# CPN_v2.net
KiCad netlist of a schematic drawn in EAGLE
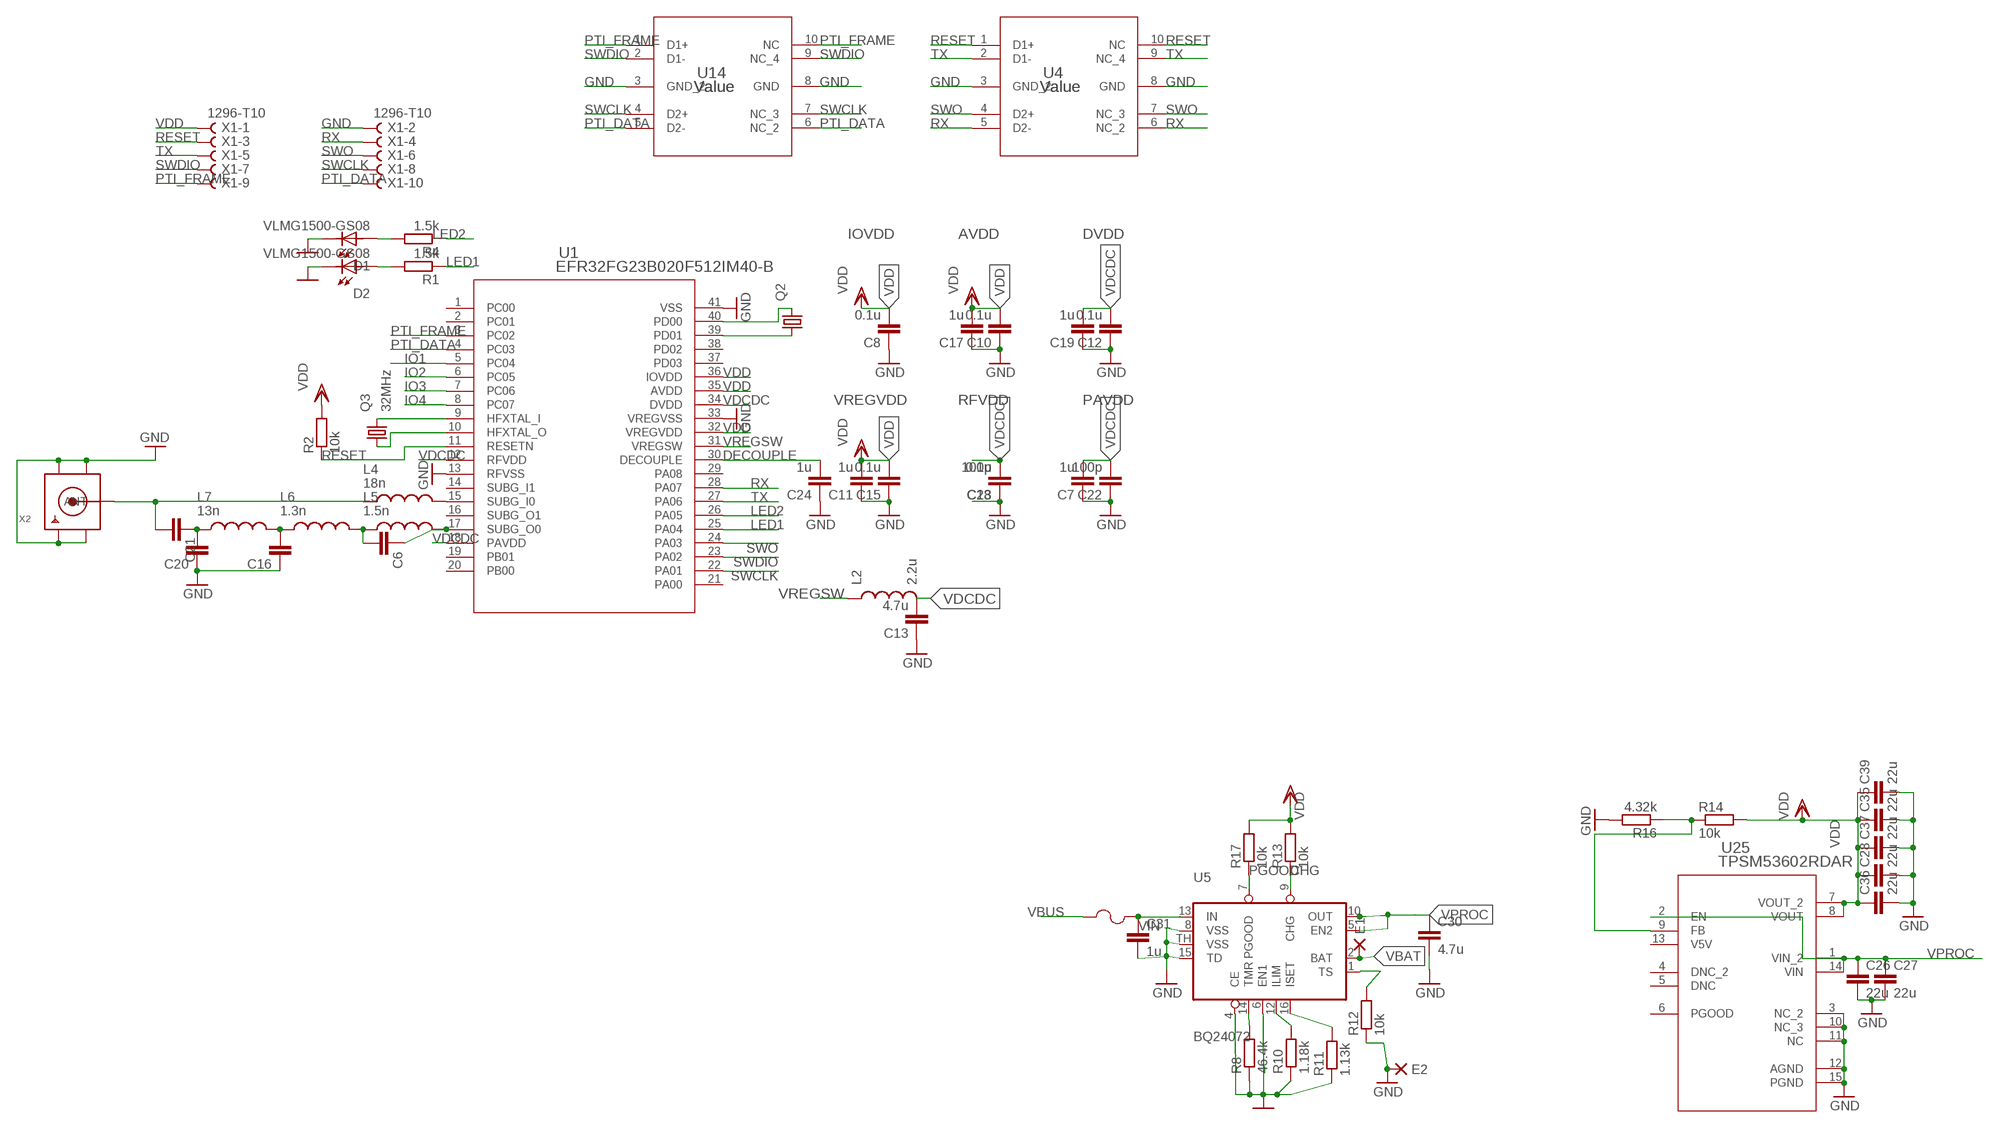
[diagram p0: schematic, sheet 1, part 1 of 2]
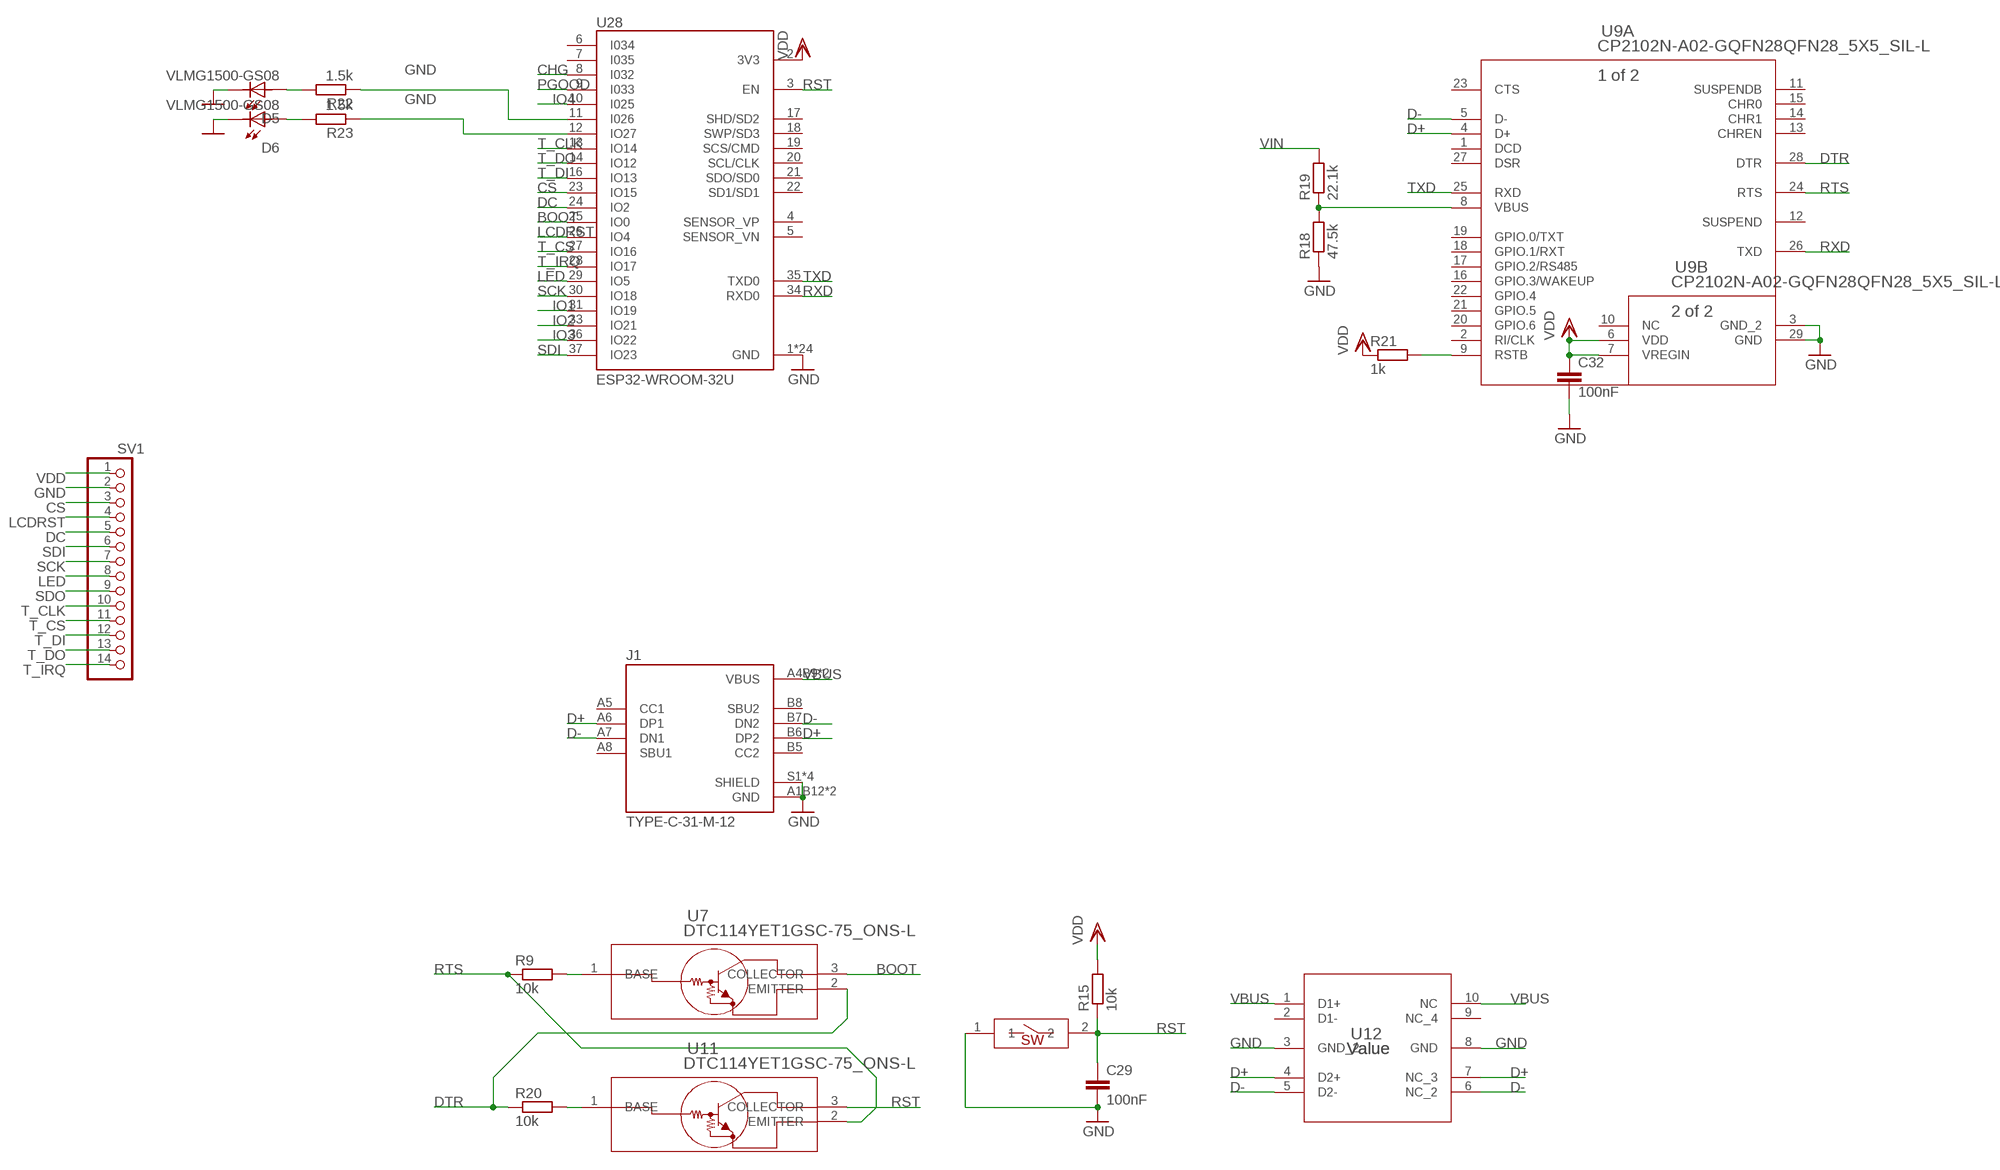
[diagram p1: schematic, sheet 1, part 2 of 2]

(export (version "E")
  (design (tool "Eeschema 10.0.6"))
  (components
    (comp (ref "C6")
      (value "1.9p")
      (footprint "eagle-import:C0402")
      (libsource (lib "eagle-import") (part "CC0402"))
    )
    (comp (ref "C7")
      (value "1u")
      (footprint "eagle-import:C0402")
      (libsource (lib "eagle-import") (part "CC0402"))
    )
    (comp (ref "C8")
      (value "0.1u")
      (footprint "eagle-import:C0402")
      (libsource (lib "eagle-import") (part "CC0402"))
    )
    (comp (ref "C10")
      (value "0.1u")
      (footprint "eagle-import:C0402")
      (libsource (lib "eagle-import") (part "CC0402"))
    )
    (comp (ref "C11")
      (value "1u")
      (footprint "eagle-import:C0402")
      (libsource (lib "eagle-import") (part "CC0402"))
    )
    (comp (ref "C12")
      (value "0.1u")
      (footprint "eagle-import:C0402")
      (libsource (lib "eagle-import") (part "CC0402"))
    )
    (comp (ref "C13")
      (value "4.7u")
      (footprint "eagle-import:C0603R")
      (libsource (lib "eagle-import") (part "CC0603R"))
    )
    (comp (ref "C15")
      (value "0.1u")
      (footprint "eagle-import:C0402")
      (libsource (lib "eagle-import") (part "CC0402"))
    )
    (comp (ref "C16")
      (value "7.2p")
      (footprint "eagle-import:C0402")
      (libsource (lib "eagle-import") (part "CC0402"))
    )
    (comp (ref "C17")
      (value "1u")
      (footprint "eagle-import:C0402")
      (libsource (lib "eagle-import") (part "CC0402"))
    )
    (comp (ref "C18")
      (value "0.1u")
      (footprint "eagle-import:C0402")
      (libsource (lib "eagle-import") (part "CC0402"))
    )
    (comp (ref "C19")
      (value "1u")
      (footprint "eagle-import:C0402")
      (libsource (lib "eagle-import") (part "CC0402"))
    )
    (comp (ref "C20")
      (value "1.3p")
      (footprint "eagle-import:C0402")
      (libsource (lib "eagle-import") (part "CC0402"))
    )
    (comp (ref "C21")
      (value "220p")
      (footprint "eagle-import:C0402")
      (libsource (lib "eagle-import") (part "CC0402"))
    )
    (comp (ref "C22")
      (value "100p")
      (footprint "eagle-import:C0402")
      (libsource (lib "eagle-import") (part "CC0402"))
    )
    (comp (ref "C23")
      (value "100p")
      (footprint "eagle-import:C0402")
      (libsource (lib "eagle-import") (part "CC0402"))
    )
    (comp (ref "C24")
      (value "1u")
      (footprint "eagle-import:C0402")
      (libsource (lib "eagle-import") (part "CC0402"))
    )
    (comp (ref "C26")
      (value "22u")
      (footprint "eagle-import:C0603R")
      (libsource (lib "eagle-import") (part "CC0603R"))
    )
    (comp (ref "C27")
      (value "22u")
      (footprint "eagle-import:C0603R")
      (libsource (lib "eagle-import") (part "CC0603R"))
    )
    (comp (ref "C28")
      (value "22u")
      (footprint "eagle-import:C0603R")
      (libsource (lib "eagle-import") (part "CC0603R"))
    )
    (comp (ref "C29")
      (value "100nF")
      (footprint "eagle-import:C0402")
      (libsource (lib "eagle-import") (part "CC0402"))
    )
    (comp (ref "C30")
      (value "4.7u")
      (footprint "eagle-import:C0402")
      (libsource (lib "eagle-import") (part "CC0402"))
    )
    (comp (ref "C31")
      (value "1u")
      (footprint "eagle-import:C0402")
      (libsource (lib "eagle-import") (part "CC0402"))
    )
    (comp (ref "C32")
      (value "100nF")
      (footprint "eagle-import:C0402")
      (libsource (lib "eagle-import") (part "CC0402"))
    )
    (comp (ref "C35")
      (value "22u")
      (footprint "eagle-import:C0603R")
      (libsource (lib "eagle-import") (part "CC0603R"))
    )
    (comp (ref "C36")
      (value "22u")
      (footprint "eagle-import:C0603R")
      (libsource (lib "eagle-import") (part "CC0603R"))
    )
    (comp (ref "C37")
      (value "22u")
      (footprint "eagle-import:C0603R")
      (libsource (lib "eagle-import") (part "CC0603R"))
    )
    (comp (ref "C39")
      (value "22u")
      (footprint "eagle-import:C0603R")
      (libsource (lib "eagle-import") (part "CC0603R"))
    )
    (comp (ref "D1")
      (value "VLMG1500-GS08")
      (footprint "eagle-import:LEDC1005X35N")
      (fields (field (name "MF") "Vishay"))
      (libsource (lib "eagle-import") (part "VLMG1500-GS08"))
    )
    (comp (ref "D2")
      (value "VLMG1500-GS08")
      (footprint "eagle-import:LEDC1005X35N")
      (fields (field (name "MF") "Vishay"))
      (libsource (lib "eagle-import") (part "VLMG1500-GS08"))
    )
    (comp (ref "D5")
      (value "VLMG1500-GS08")
      (footprint "eagle-import:LEDC1005X35N")
      (fields (field (name "MF") "Vishay"))
      (libsource (lib "eagle-import") (part "VLMG1500-GS08"))
    )
    (comp (ref "D6")
      (value "VLMG1500-GS08")
      (footprint "eagle-import:LEDC1005X35N")
      (fields (field (name "MF") "Vishay"))
      (libsource (lib "eagle-import") (part "VLMG1500-GS08"))
    )
    (comp (ref "E1")
      (value "DPADS_PAD-0400-S")
      (footprint "eagle-import:DPADS_0400-S")
      (libsource (lib "eagle-import") (part "DPADS_PAD-0400-S"))
    )
    (comp (ref "E2")
      (value "DPADS_PAD-0400-S")
      (footprint "eagle-import:DPADS_0400-S")
      (libsource (lib "eagle-import") (part "DPADS_PAD-0400-S"))
    )
    (comp (ref "F2")
      (value "1210L050YR1210LSERIES_LTF-L")
      (footprint "eagle-import:1210LSERIES_LTF-L")
      (fields (field (name "MANUFACTURER_PART_NUMBER") "1210L050YR"))
      (libsource (lib "eagle-import") (part "1210L050YR1210LSERIES_LTF-L"))
    )
    (comp (ref "J1")
      (value "TYPE-C-31-M-12")
      (footprint "eagle-import:HRO_TYPE-C-31-M-12")
      (fields (field (name "MF") "HRO Electronics Co., Ltd."))
      (libsource (lib "eagle-import") (part "TYPE-C-31-M-12"))
    )
    (comp (ref "L2")
      (value "2.2u")
      (footprint "eagle-import:L0603")
      (libsource (lib "eagle-import") (part "INDUCTOR"))
    )
    (comp (ref "L4")
      (value "18n")
      (footprint "eagle-import:INDC0402X26N")
      (fields (field (name "MF") "TDK") (field (name "MP") "MHQ0402P7N5JT000"))
      (libsource (lib "eagle-import") (part "MHQ0402P7N5JT000"))
    )
    (comp (ref "L5")
      (value "1.5n")
      (footprint "eagle-import:INDC0402X26N")
      (fields (field (name "MF") "TDK") (field (name "MP") "MHQ0402P7N5JT000"))
      (libsource (lib "eagle-import") (part "MHQ0402P7N5JT000"))
    )
    (comp (ref "L6")
      (value "1.3n")
      (footprint "eagle-import:INDC0402X26N")
      (fields (field (name "MF") "TDK") (field (name "MP") "MHQ0402P7N5JT000"))
      (libsource (lib "eagle-import") (part "MHQ0402P7N5JT000"))
    )
    (comp (ref "L7")
      (value "13n")
      (footprint "eagle-import:INDC0402X26N")
      (fields (field (name "MF") "TDK") (field (name "MP") "MHQ0402P7N5JT000"))
      (libsource (lib "eagle-import") (part "MHQ0402P7N5JT000"))
    )
    (comp (ref "Q2")
      (value "KX-327-RT")
      (footprint "eagle-import:2.0X1.2")
      (libsource (lib "eagle-import") (part "KX-327-RT"))
    )
    (comp (ref "Q3")
      (value "32MHz")
      (footprint "eagle-import:2.0X1.6_KX-5")
      (libsource (lib "eagle-import") (part "KX-5"))
    )
    (comp (ref "R1")
      (value "1.5k")
      (footprint "eagle-import:R0402")
      (libsource (lib "eagle-import") (part "RR0402"))
    )
    (comp (ref "R2")
      (value "10k")
      (footprint "eagle-import:R0402")
      (libsource (lib "eagle-import") (part "RR0402"))
    )
    (comp (ref "R4")
      (value "1.5k")
      (footprint "eagle-import:R0402")
      (libsource (lib "eagle-import") (part "RR0402"))
    )
    (comp (ref "R8")
      (value "46.4k")
      (footprint "eagle-import:R0402")
      (libsource (lib "eagle-import") (part "RR0402"))
    )
    (comp (ref "R9")
      (value "10k")
      (footprint "eagle-import:R0402")
      (libsource (lib "eagle-import") (part "RR0402"))
    )
    (comp (ref "R10")
      (value "1.18k")
      (footprint "eagle-import:R0402")
      (libsource (lib "eagle-import") (part "RR0402"))
    )
    (comp (ref "R11")
      (value "1.13k")
      (footprint "eagle-import:R0402")
      (libsource (lib "eagle-import") (part "RR0402"))
    )
    (comp (ref "R12")
      (value "10k")
      (footprint "eagle-import:R0402")
      (libsource (lib "eagle-import") (part "RR0402"))
    )
    (comp (ref "R13")
      (value "10k")
      (footprint "eagle-import:R0402")
      (libsource (lib "eagle-import") (part "RR0402"))
    )
    (comp (ref "R14")
      (value "10k")
      (footprint "eagle-import:R0402")
      (libsource (lib "eagle-import") (part "RR0402"))
    )
    (comp (ref "R15")
      (value "10k")
      (footprint "eagle-import:R0402")
      (libsource (lib "eagle-import") (part "RR0402"))
    )
    (comp (ref "R16")
      (value "4.32k")
      (footprint "eagle-import:R0402")
      (libsource (lib "eagle-import") (part "RR0402"))
    )
    (comp (ref "R17")
      (value "10k")
      (footprint "eagle-import:R0402")
      (libsource (lib "eagle-import") (part "RR0402"))
    )
    (comp (ref "R18")
      (value "47.5k")
      (footprint "eagle-import:R0402")
      (libsource (lib "eagle-import") (part "RR0402"))
    )
    (comp (ref "R19")
      (value "22.1k")
      (footprint "eagle-import:R0402")
      (libsource (lib "eagle-import") (part "RR0402"))
    )
    (comp (ref "R20")
      (value "10k")
      (footprint "eagle-import:R0402")
      (libsource (lib "eagle-import") (part "RR0402"))
    )
    (comp (ref "R21")
      (value "1k")
      (footprint "eagle-import:R0402")
      (libsource (lib "eagle-import") (part "RR0402"))
    )
    (comp (ref "R22")
      (value "1.5k")
      (footprint "eagle-import:R0402")
      (libsource (lib "eagle-import") (part "RR0402"))
    )
    (comp (ref "R23")
      (value "1.5k")
      (footprint "eagle-import:R0402")
      (libsource (lib "eagle-import") (part "RR0402"))
    )
    (comp (ref "RESET")
      (value "SMDSWITCH")
      (footprint "eagle-import:RESC4217X170")
      (libsource (lib "eagle-import") (part "SMDSWITCH"))
    )
    (comp (ref "SV1")
      (value "PINHD-1X14")
      (footprint "eagle-import:1X14")
      (libsource (lib "eagle-import") (part "PINHD-1X14"))
    )
    (comp (ref "U1")
      (value "EFR32FG23B020F512IM40-B")
      (footprint "eagle-import:QFN_40_SIL")
      (fields (field (name "COPYRIGHT") "Copyright (C) 2022 Ultra Librarian. All rights reserved."))
      (libsource (lib "eagle-import") (part "EFR32FG23B020F512IM40-B"))
    )
    (comp (ref "U4")
      (value "Value")
      (footprint "eagle-import:DQA0010A")
      (fields (field (name "MANUFACTURER") "Texas Instruments") (field (name "PARTNUMBER") "ESD204DQAR"))
      (libsource (lib "eagle-import") (part "ESD204DQAR"))
    )
    (comp (ref "U5")
      (value "BQ24072")
      (footprint "eagle-import:S-PVQFN-N16")
      (libsource (lib "eagle-import") (part "BQ24072"))
    )
    (comp (ref "U7")
      (value "DTC114YET1GSC-75_ONS-L")
      (footprint "eagle-import:SC-75_ONS-L")
      (fields
        (field (name "MANUFACTURER_PART_NUMBER") "DTC114YET1G")
        (field (name "COPYRIGHT") "Copyright (C) 2018 Accelerated Designs. All rights reserved")
      )
      (libsource (lib "eagle-import") (part "DTC114YET1GSC-75_ONS-L"))
    )
    (comp (ref "U9")
      (value "CP2102N-A02-GQFN28QFN28_5X5_SIL-L")
      (footprint "eagle-import:QFN28_5X5_SIL-L")
      (fields
        (field (name "MANUFACTURER_PART_NUMBER") "CP2102N-A02-GQFN28")
        (field (name "COPYRIGHT") "Copyright (C) 2018 Accelerated Designs. All rights reserved")
      )
      (libsource (lib "eagle-import") (part "CP2102N-A02-GQFN28QFN28_5X5_SIL-L"))
    )
    (comp (ref "U11")
      (value "DTC114YET1GSC-75_ONS-L")
      (footprint "eagle-import:SC-75_ONS-L")
      (fields
        (field (name "MANUFACTURER_PART_NUMBER") "DTC114YET1G")
        (field (name "COPYRIGHT") "Copyright (C) 2018 Accelerated Designs. All rights reserved")
      )
      (libsource (lib "eagle-import") (part "DTC114YET1GSC-75_ONS-L"))
    )
    (comp (ref "U12")
      (value "Value")
      (footprint "eagle-import:DQA0010A")
      (fields (field (name "MANUFACTURER") "Texas Instruments") (field (name "PARTNUMBER") "ESD204DQAR"))
      (libsource (lib "eagle-import") (part "ESD204DQAR"))
    )
    (comp (ref "U14")
      (value "Value")
      (footprint "eagle-import:DQA0010A")
      (fields (field (name "MANUFACTURER") "Texas Instruments") (field (name "PARTNUMBER") "ESD204DQAR"))
      (libsource (lib "eagle-import") (part "ESD204DQAR"))
    )
    (comp (ref "U25")
      (value "TPSM53602RDAR")
      (footprint "eagle-import:B3QFN15_RDA_TEX")
      (fields (field (name "COPYRIGHT") "Copyright (C) 2018 Accelerated Designs. All rights reserved"))
      (libsource (lib "eagle-import") (part "TPSM53602RDAR"))
    )
    (comp (ref "U28")
      (value "ESP32-WROOM-32U")
      (footprint "eagle-import:XCVR_ESP32-WROOM-32U")
      (fields (field (name "MF") "Espressif Systems"))
      (libsource (lib "eagle-import") (part "ESP32-WROOM-32U"))
    )
    (comp (ref "X1")
      (value "1296-T10")
      (footprint "eagle-import:1296-10")
      (libsource (lib "eagle-import") (part "1296-T10"))
    )
    (comp (ref "X2")
      (value "SMACONNECTOR")
      (footprint "eagle-import:SMA90_DIP")
      (libsource (lib "eagle-import") (part "SMACONNECTOR"))
    )
  )
  (nets
    (net (code "1") (name "/BOOT") (class "Default")
      (node (ref "U28") (pin "25") (pinfunction "IO0_25") (pintype "bidirectional"))
      (node (ref "U7") (pin "3") (pinfunction "COLLECTOR_3") (pintype "output"))
    )
    (net (code "2") (name "/CHG") (class "Default")
      (node (ref "R13") (pin "1") (pinfunction "1_1") (pintype "passive"))
      (node (ref "U28") (pin "8") (pinfunction "I032_8") (pintype "bidirectional"))
      (node (ref "U5") (pin "9") (pinfunction "CHG_9") (pintype "bidirectional"))
    )
    (net (code "3") (name "/CS") (class "Default")
      (node (ref "SV1") (pin "3") (pinfunction "3_3") (pintype "passive"))
      (node (ref "U28") (pin "23") (pinfunction "IO15_23") (pintype "bidirectional"))
    )
    (net (code "4") (name "/D+") (class "Default")
      (node (ref "J1") (pin "A6") (pinfunction "DP1_A6") (pintype "bidirectional"))
      (node (ref "J1") (pin "B6") (pinfunction "DP2_B6") (pintype "bidirectional"))
      (node (ref "U12") (pin "4") (pinfunction "D2+_4") (pintype "bidirectional"))
      (node (ref "U12") (pin "7") (pinfunction "NC_3_7") (pintype "passive"))
      (node (ref "U9") (pin "4") (pinfunction "D+_4") (pintype "input"))
    )
    (net (code "5") (name "/D-") (class "Default")
      (node (ref "J1") (pin "A7") (pinfunction "DN1_A7") (pintype "bidirectional"))
      (node (ref "J1") (pin "B7") (pinfunction "DN2_B7") (pintype "bidirectional"))
      (node (ref "U12") (pin "5") (pinfunction "D2-_5") (pintype "bidirectional"))
      (node (ref "U12") (pin "6") (pinfunction "NC_2_6") (pintype "passive"))
      (node (ref "U9") (pin "5") (pinfunction "D-_5") (pintype "input"))
    )
    (net (code "6") (name "/DC") (class "Default")
      (node (ref "SV1") (pin "5") (pinfunction "5_5") (pintype "passive"))
      (node (ref "U28") (pin "24") (pinfunction "IO2_24") (pintype "bidirectional"))
    )
    (net (code "7") (name "/DECOUPLE") (class "Default")
      (node (ref "C24") (pin "2") (pinfunction "2_2") (pintype "passive"))
      (node (ref "U1") (pin "30") (pinfunction "DECOUPLE_30") (pintype "passive"))
    )
    (net (code "8") (name "/DTR") (class "Default")
      (node (ref "R20") (pin "1") (pinfunction "1_1") (pintype "passive"))
      (node (ref "U7") (pin "2") (pinfunction "EMITTER_2") (pintype "passive"))
      (node (ref "U9") (pin "28") (pinfunction "DTR_28") (pintype "output"))
    )
    (net (code "9") (name "/IO1") (class "Default")
      (node (ref "U1") (pin "5") (pinfunction "PC04_5") (pintype "bidirectional"))
      (node (ref "U28") (pin "31") (pinfunction "IO19_31") (pintype "bidirectional"))
    )
    (net (code "10") (name "/IO2") (class "Default")
      (node (ref "U1") (pin "6") (pinfunction "PC05_6") (pintype "bidirectional"))
      (node (ref "U28") (pin "33") (pinfunction "IO21_33") (pintype "bidirectional"))
    )
    (net (code "11") (name "/IO3") (class "Default")
      (node (ref "U1") (pin "7") (pinfunction "PC06_7") (pintype "bidirectional"))
      (node (ref "U28") (pin "36") (pinfunction "IO22_36") (pintype "bidirectional"))
    )
    (net (code "12") (name "/IO4") (class "Default")
      (node (ref "U1") (pin "8") (pinfunction "PC07_8") (pintype "bidirectional"))
      (node (ref "U28") (pin "10") (pinfunction "I025_10") (pintype "bidirectional"))
    )
    (net (code "13") (name "/LCDRST") (class "Default")
      (node (ref "SV1") (pin "4") (pinfunction "4_4") (pintype "passive"))
      (node (ref "U28") (pin "26") (pinfunction "IO4_26") (pintype "bidirectional"))
    )
    (net (code "14") (name "/LED") (class "Default")
      (node (ref "SV1") (pin "8") (pinfunction "8_8") (pintype "passive"))
      (node (ref "U28") (pin "29") (pinfunction "IO5_29") (pintype "bidirectional"))
    )
    (net (code "15") (name "/LED1") (class "Default")
      (node (ref "R1") (pin "1") (pinfunction "1_1") (pintype "passive"))
      (node (ref "U1") (pin "25") (pinfunction "PA04_25") (pintype "bidirectional"))
    )
    (net (code "16") (name "/LED2") (class "Default")
      (node (ref "R4") (pin "1") (pinfunction "1_1") (pintype "passive"))
      (node (ref "U1") (pin "26") (pinfunction "PA05_26") (pintype "bidirectional"))
    )
    (net (code "17") (name "/PGOOD") (class "Default")
      (node (ref "R17") (pin "1") (pinfunction "1_1") (pintype "passive"))
      (node (ref "U28") (pin "9") (pinfunction "I033_9") (pintype "bidirectional"))
      (node (ref "U5") (pin "7") (pinfunction "PGOOD_7") (pintype "bidirectional"))
    )
    (net (code "18") (name "/PTI_DATA") (class "Default")
      (node (ref "U1") (pin "4") (pinfunction "PC03_4") (pintype "bidirectional"))
      (node (ref "U14") (pin "5") (pinfunction "D2-_5") (pintype "bidirectional"))
      (node (ref "U14") (pin "6") (pinfunction "NC_2_6") (pintype "passive"))
      (node (ref "X1") (pin "10") (pinfunction "B_10") (pintype "passive"))
    )
    (net (code "19") (name "/PTI_FRAME") (class "Default")
      (node (ref "U1") (pin "3") (pinfunction "PC02_3") (pintype "bidirectional"))
      (node (ref "U14") (pin "1") (pinfunction "D1+_1") (pintype "bidirectional"))
      (node (ref "U14") (pin "10") (pinfunction "NC_10") (pintype "passive"))
      (node (ref "X1") (pin "9") (pinfunction "B_9") (pintype "passive"))
    )
    (net (code "20") (name "/RESET") (class "Default")
      (node (ref "R2") (pin "1") (pinfunction "1_1") (pintype "passive"))
      (node (ref "U1") (pin "11") (pinfunction "RESETN_11") (pintype "input"))
      (node (ref "U4") (pin "1") (pinfunction "D1+_1") (pintype "bidirectional"))
      (node (ref "U4") (pin "10") (pinfunction "NC_10") (pintype "passive"))
      (node (ref "X1") (pin "3") (pinfunction "B_3") (pintype "passive"))
    )
    (net (code "21") (name "/RST") (class "Default")
      (node (ref "C29") (pin "1") (pinfunction "1_1") (pintype "passive"))
      (node (ref "R15") (pin "1") (pinfunction "1_1") (pintype "passive"))
      (node (ref "RESET") (pin "2") (pinfunction "2_2") (pintype "bidirectional"))
      (node (ref "U11") (pin "3") (pinfunction "COLLECTOR_3") (pintype "output"))
      (node (ref "U28") (pin "3") (pinfunction "EN_3") (pintype "input"))
    )
    (net (code "22") (name "/RTS") (class "Default")
      (node (ref "R9") (pin "1") (pinfunction "1_1") (pintype "passive"))
      (node (ref "U11") (pin "2") (pinfunction "EMITTER_2") (pintype "passive"))
      (node (ref "U9") (pin "24") (pinfunction "RTS_24") (pintype "output"))
    )
    (net (code "23") (name "/RX") (class "Default")
      (node (ref "U1") (pin "28") (pinfunction "PA07_28") (pintype "bidirectional"))
      (node (ref "U4") (pin "5") (pinfunction "D2-_5") (pintype "bidirectional"))
      (node (ref "U4") (pin "6") (pinfunction "NC_2_6") (pintype "passive"))
      (node (ref "X1") (pin "4") (pinfunction "B_4") (pintype "passive"))
    )
    (net (code "24") (name "/RXD") (class "Default")
      (node (ref "U28") (pin "34") (pinfunction "RXD0_34") (pintype "bidirectional"))
      (node (ref "U9") (pin "26") (pinfunction "TXD_26") (pintype "output"))
    )
    (net (code "25") (name "/SCK") (class "Default")
      (node (ref "SV1") (pin "7") (pinfunction "7_7") (pintype "passive"))
      (node (ref "U28") (pin "30") (pinfunction "IO18_30") (pintype "bidirectional"))
    )
    (net (code "26") (name "/SDI") (class "Default")
      (node (ref "SV1") (pin "6") (pinfunction "6_6") (pintype "passive"))
      (node (ref "U28") (pin "37") (pinfunction "IO23_37") (pintype "bidirectional"))
    )
    (net (code "27") (name "/SDO") (class "Default")
      (node (ref "SV1") (pin "9") (pinfunction "9_9") (pintype "passive"))
    )
    (net (code "28") (name "/SWCLK") (class "Default")
      (node (ref "U1") (pin "22") (pinfunction "PA01_22") (pintype "bidirectional"))
      (node (ref "U14") (pin "4") (pinfunction "D2+_4") (pintype "bidirectional"))
      (node (ref "U14") (pin "7") (pinfunction "NC_3_7") (pintype "passive"))
      (node (ref "X1") (pin "8") (pinfunction "B_8") (pintype "passive"))
    )
    (net (code "29") (name "/SWDIO") (class "Default")
      (node (ref "U1") (pin "23") (pinfunction "PA02_23") (pintype "bidirectional"))
      (node (ref "U14") (pin "2") (pinfunction "D1-_2") (pintype "bidirectional"))
      (node (ref "U14") (pin "9") (pinfunction "NC_4_9") (pintype "passive"))
      (node (ref "X1") (pin "7") (pinfunction "B_7") (pintype "passive"))
    )
    (net (code "30") (name "/SWO") (class "Default")
      (node (ref "U1") (pin "24") (pinfunction "PA03_24") (pintype "bidirectional"))
      (node (ref "U4") (pin "4") (pinfunction "D2+_4") (pintype "bidirectional"))
      (node (ref "U4") (pin "7") (pinfunction "NC_3_7") (pintype "passive"))
      (node (ref "X1") (pin "6") (pinfunction "B_6") (pintype "passive"))
    )
    (net (code "31") (name "/TX") (class "Default")
      (node (ref "U1") (pin "27") (pinfunction "PA06_27") (pintype "bidirectional"))
      (node (ref "U4") (pin "2") (pinfunction "D1-_2") (pintype "bidirectional"))
      (node (ref "U4") (pin "9") (pinfunction "NC_4_9") (pintype "passive"))
      (node (ref "X1") (pin "5") (pinfunction "B_5") (pintype "passive"))
    )
    (net (code "32") (name "/TXD") (class "Default")
      (node (ref "U28") (pin "35") (pinfunction "TXD0_35") (pintype "bidirectional"))
      (node (ref "U9") (pin "25") (pinfunction "RXD_25") (pintype "input"))
    )
    (net (code "33") (name "/T_CLK") (class "Default")
      (node (ref "SV1") (pin "10") (pinfunction "10_10") (pintype "passive"))
      (node (ref "U28") (pin "13") (pinfunction "IO14_13") (pintype "bidirectional"))
    )
    (net (code "34") (name "/T_CS") (class "Default")
      (node (ref "SV1") (pin "11") (pinfunction "11_11") (pintype "passive"))
      (node (ref "U28") (pin "27") (pinfunction "IO16_27") (pintype "bidirectional"))
    )
    (net (code "35") (name "/T_DI") (class "Default")
      (node (ref "SV1") (pin "12") (pinfunction "12_12") (pintype "passive"))
      (node (ref "U28") (pin "16") (pinfunction "IO13_16") (pintype "bidirectional"))
    )
    (net (code "36") (name "/T_DO") (class "Default")
      (node (ref "SV1") (pin "13") (pinfunction "13_13") (pintype "passive"))
      (node (ref "U28") (pin "14") (pinfunction "IO12_14") (pintype "bidirectional"))
    )
    (net (code "37") (name "/T_IRQ") (class "Default")
      (node (ref "SV1") (pin "14") (pinfunction "14_14") (pintype "passive"))
      (node (ref "U28") (pin "28") (pinfunction "IO17_28") (pintype "bidirectional"))
    )
    (net (code "38") (name "/VBUS") (class "Default")
      (node (ref "F2") (pin "1") (pinfunction "1_1") (pintype "passive"))
      (node (ref "J1") (pin "A4B9") (pinfunction "VBUS_A4B9") (pintype "power_in"))
      (node (ref "J1") (pin "B4A9") (pinfunction "VBUS_B4A9") (pintype "power_in"))
      (node (ref "U12") (pin "1") (pinfunction "D1+_1") (pintype "bidirectional"))
      (node (ref "U12") (pin "10") (pinfunction "NC_10") (pintype "passive"))
    )
    (net (code "39") (name "/VIN") (class "Default")
      (node (ref "C31") (pin "1") (pinfunction "1_1") (pintype "passive"))
      (node (ref "F2") (pin "2") (pinfunction "2_2") (pintype "passive"))
      (node (ref "R19") (pin "2") (pinfunction "2_2") (pintype "passive"))
      (node (ref "U5") (pin "13") (pinfunction "IN_13") (pintype "input"))
    )
    (net (code "40") (name "/VREGSW") (class "Default")
      (node (ref "L2") (pin "1") (pinfunction "1_1") (pintype "passive"))
      (node (ref "U1") (pin "31") (pinfunction "VREGSW_31") (pintype "power_in"))
    )
    (net (code "41") (name "GND") (class "Default")
      (node (ref "C10") (pin "1") (pinfunction "1_1") (pintype "passive"))
      (node (ref "C11") (pin "1") (pinfunction "1_1") (pintype "passive"))
      (node (ref "C12") (pin "1") (pinfunction "1_1") (pintype "passive"))
      (node (ref "C13") (pin "1") (pinfunction "1_1") (pintype "passive"))
      (node (ref "C15") (pin "1") (pinfunction "1_1") (pintype "passive"))
      (node (ref "C16") (pin "1") (pinfunction "1_1") (pintype "passive"))
      (node (ref "C17") (pin "1") (pinfunction "1_1") (pintype "passive"))
      (node (ref "C18") (pin "1") (pinfunction "1_1") (pintype "passive"))
      (node (ref "C19") (pin "1") (pinfunction "1_1") (pintype "passive"))
      (node (ref "C20") (pin "1") (pinfunction "1_1") (pintype "passive"))
      (node (ref "C22") (pin "1") (pinfunction "1_1") (pintype "passive"))
      (node (ref "C23") (pin "1") (pinfunction "1_1") (pintype "passive"))
      (node (ref "C24") (pin "1") (pinfunction "1_1") (pintype "passive"))
      (node (ref "C26") (pin "2") (pinfunction "2_2") (pintype "passive"))
      (node (ref "C27") (pin "2") (pinfunction "2_2") (pintype "passive"))
      (node (ref "C28") (pin "2") (pinfunction "2_2") (pintype "passive"))
      (node (ref "C29") (pin "2") (pinfunction "2_2") (pintype "passive"))
      (node (ref "C30") (pin "2") (pinfunction "2_2") (pintype "passive"))
      (node (ref "C31") (pin "2") (pinfunction "2_2") (pintype "passive"))
      (node (ref "C32") (pin "2") (pinfunction "2_2") (pintype "passive"))
      (node (ref "C35") (pin "2") (pinfunction "2_2") (pintype "passive"))
      (node (ref "C36") (pin "2") (pinfunction "2_2") (pintype "passive"))
      (node (ref "C37") (pin "2") (pinfunction "2_2") (pintype "passive"))
      (node (ref "C39") (pin "2") (pinfunction "2_2") (pintype "passive"))
      (node (ref "C7") (pin "1") (pinfunction "1_1") (pintype "passive"))
      (node (ref "C8") (pin "1") (pinfunction "1_1") (pintype "passive"))
      (node (ref "D1") (pin "2") (pinfunction "2_2") (pintype "passive"))
      (node (ref "D2") (pin "2") (pinfunction "2_2") (pintype "passive"))
      (node (ref "D5") (pin "2") (pinfunction "2_2") (pintype "passive"))
      (node (ref "D6") (pin "2") (pinfunction "2_2") (pintype "passive"))
      (node (ref "E2") (pin "PAD") (pinfunction "P_PAD") (pintype "passive"))
      (node (ref "J1") (pin "A1B12") (pinfunction "GND_A1B12") (pintype "power_in"))
      (node (ref "J1") (pin "B1A12") (pinfunction "GND_B1A12") (pintype "power_in"))
      (node (ref "J1") (pin "S1") (pinfunction "SHIELD_S1") (pintype "passive"))
      (node (ref "J1") (pin "S2") (pinfunction "SHIELD_S2") (pintype "passive"))
      (node (ref "J1") (pin "S3") (pinfunction "SHIELD_S3") (pintype "passive"))
      (node (ref "J1") (pin "S4") (pinfunction "SHIELD_S4") (pintype "passive"))
      (node (ref "R10") (pin "1") (pinfunction "1_1") (pintype "passive"))
      (node (ref "R11") (pin "1") (pinfunction "1_1") (pintype "passive"))
      (node (ref "R12") (pin "1") (pinfunction "1_1") (pintype "passive"))
      (node (ref "R16") (pin "2") (pinfunction "2_2") (pintype "passive"))
      (node (ref "R18") (pin "1") (pinfunction "1_1") (pintype "passive"))
      (node (ref "R8") (pin "1") (pinfunction "1_1") (pintype "passive"))
      (node (ref "RESET") (pin "1") (pinfunction "1_1") (pintype "bidirectional"))
      (node (ref "SV1") (pin "2") (pinfunction "2_2") (pintype "passive"))
      (node (ref "U1") (pin "13") (pinfunction "RFVSS_13") (pintype "power_in"))
      (node (ref "U1") (pin "33") (pinfunction "VREGVSS_33") (pintype "power_in"))
      (node (ref "U1") (pin "41") (pinfunction "VSS_41") (pintype "power_in"))
      (node (ref "U12") (pin "3") (pinfunction "GND_2_3") (pintype "power_in"))
      (node (ref "U12") (pin "8") (pinfunction "GND_8") (pintype "power_in"))
      (node (ref "U14") (pin "3") (pinfunction "GND_2_3") (pintype "power_in"))
      (node (ref "U14") (pin "8") (pinfunction "GND_8") (pintype "power_in"))
      (node (ref "U25") (pin "10") (pinfunction "NC_3_10") (pintype "passive"))
      (node (ref "U25") (pin "11") (pinfunction "NC_11") (pintype "passive"))
      (node (ref "U25") (pin "12") (pinfunction "AGND_12") (pintype "passive"))
      (node (ref "U25") (pin "15") (pinfunction "PGND_15") (pintype "passive"))
      (node (ref "U25") (pin "3") (pinfunction "NC_2_3") (pintype "passive"))
      (node (ref "U28") (pin "1") (pinfunction "GND_1") (pintype "power_in"))
      (node (ref "U28") (pin "15") (pinfunction "GND_15") (pintype "power_in"))
      (node (ref "U28") (pin "38") (pinfunction "GND_38") (pintype "power_in"))
      (node (ref "U28") (pin "G.1") (pinfunction "GND_G.1") (pintype "power_in"))
      (node (ref "U28") (pin "G.10") (pinfunction "GND_G.10") (pintype "power_in"))
      (node (ref "U28") (pin "G.11") (pinfunction "GND_G.11") (pintype "power_in"))
      (node (ref "U28") (pin "G.12") (pinfunction "GND_G.12") (pintype "power_in"))
      (node (ref "U28") (pin "G.13") (pinfunction "GND_G.13") (pintype "power_in"))
      (node (ref "U28") (pin "G.14") (pinfunction "GND_G.14") (pintype "power_in"))
      (node (ref "U28") (pin "G.15") (pinfunction "GND_G.15") (pintype "power_in"))
      (node (ref "U28") (pin "G.16") (pinfunction "GND_G.16") (pintype "power_in"))
      (node (ref "U28") (pin "G.17") (pinfunction "GND_G.17") (pintype "power_in"))
      (node (ref "U28") (pin "G.18") (pinfunction "GND_G.18") (pintype "power_in"))
      (node (ref "U28") (pin "G.19") (pinfunction "GND_G.19") (pintype "power_in"))
      (node (ref "U28") (pin "G.2") (pinfunction "GND_G.2") (pintype "power_in"))
      (node (ref "U28") (pin "G.20") (pinfunction "GND_G.20") (pintype "power_in"))
      (node (ref "U28") (pin "G.21") (pinfunction "GND_G.21") (pintype "power_in"))
      (node (ref "U28") (pin "G.22") (pinfunction "GND_G.22") (pintype "power_in"))
      (node (ref "U28") (pin "G.4") (pinfunction "GND_G.4") (pintype "power_in"))
      (node (ref "U28") (pin "G.5") (pinfunction "GND_G.5") (pintype "power_in"))
      (node (ref "U28") (pin "G.6") (pinfunction "GND_G.6") (pintype "power_in"))
      (node (ref "U28") (pin "G.7") (pinfunction "GND_G.7") (pintype "power_in"))
      (node (ref "U28") (pin "G.8") (pinfunction "GND_G.8") (pintype "power_in"))
      (node (ref "U28") (pin "G.9") (pinfunction "GND_G.9") (pintype "power_in"))
      (node (ref "U4") (pin "3") (pinfunction "GND_2_3") (pintype "power_in"))
      (node (ref "U4") (pin "8") (pinfunction "GND_8") (pintype "power_in"))
      (node (ref "U5") (pin "15") (pinfunction "TD_15") (pintype "bidirectional"))
      (node (ref "U5") (pin "4") (pinfunction "CE_4") (pintype "bidirectional"))
      (node (ref "U5") (pin "6") (pinfunction "EN1_6") (pintype "bidirectional"))
      (node (ref "U5") (pin "8") (pinfunction "VSS_8") (pintype "power_in"))
      (node (ref "U5") (pin "TH") (pinfunction "VSS_TH") (pintype "power_in"))
      (node (ref "U9") (pin "29") (pinfunction "GND_29") (pintype "passive"))
      (node (ref "U9") (pin "3") (pinfunction "GND_2_3") (pintype "passive"))
      (node (ref "X1") (pin "2") (pinfunction "B_2") (pintype "passive"))
      (node (ref "X2") (pin "GND1") (pinfunction "GND1_GND1") (pintype "power_in"))
      (node (ref "X2") (pin "GND2") (pinfunction "GND2_GND2") (pintype "power_in"))
      (node (ref "X2") (pin "GND3") (pinfunction "GND3_GND3") (pintype "power_in"))
      (node (ref "X2") (pin "GND4") (pinfunction "GND4_GND4") (pintype "power_in"))
    )
    (net (code "42") (name "Net-(C6-Pad2)") (class "Default")
      (node (ref "C6") (pin "2") (pinfunction "2_2") (pintype "passive"))
      (node (ref "L5") (pin "1") (pinfunction "1_1") (pintype "passive"))
      (node (ref "L6") (pin "2") (pinfunction "2_2") (pintype "passive"))
    )
    (net (code "43") (name "Net-(C16-Pad2)") (class "Default")
      (node (ref "C16") (pin "2") (pinfunction "2_2") (pintype "passive"))
      (node (ref "L6") (pin "1") (pinfunction "1_1") (pintype "passive"))
      (node (ref "L7") (pin "2") (pinfunction "2_2") (pintype "passive"))
    )
    (net (code "44") (name "Net-(C20-Pad2)") (class "Default")
      (node (ref "C20") (pin "2") (pinfunction "2_2") (pintype "passive"))
      (node (ref "C21") (pin "1") (pinfunction "1_1") (pintype "passive"))
      (node (ref "L7") (pin "1") (pinfunction "1_1") (pintype "passive"))
    )
    (net (code "45") (name "Net-(D1-Pad1)") (class "Default")
      (node (ref "D1") (pin "1") (pinfunction "1_1") (pintype "passive"))
      (node (ref "R4") (pin "2") (pinfunction "2_2") (pintype "passive"))
    )
    (net (code "46") (name "Net-(D2-Pad1)") (class "Default")
      (node (ref "D2") (pin "1") (pinfunction "1_1") (pintype "passive"))
      (node (ref "R1") (pin "2") (pinfunction "2_2") (pintype "passive"))
    )
    (net (code "47") (name "Net-(D5-Pad1)") (class "Default")
      (node (ref "D5") (pin "1") (pinfunction "1_1") (pintype "passive"))
      (node (ref "R22") (pin "2") (pinfunction "2_2") (pintype "passive"))
    )
    (net (code "48") (name "Net-(D6-Pad1)") (class "Default")
      (node (ref "D6") (pin "1") (pinfunction "1_1") (pintype "passive"))
      (node (ref "R23") (pin "2") (pinfunction "2_2") (pintype "passive"))
    )
    (net (code "49") (name "Net-(Q3-2)") (class "Default")
      (node (ref "Q3") (pin "3") (pinfunction "2_3") (pintype "passive"))
      (node (ref "U1") (pin "9") (pinfunction "HFXTAL_I_9") (pintype "input"))
    )
    (net (code "50") (name "Net-(U1-HFXTAL_O)") (class "Default")
      (node (ref "Q3") (pin "1") (pinfunction "1_1") (pintype "passive"))
      (node (ref "U1") (pin "10") (pinfunction "HFXTAL_O_10") (pintype "output"))
    )
    (net (code "51") (name "Net-(U1-PD00)") (class "Default")
      (node (ref "Q2") (pin "2") (pinfunction "2_2") (pintype "passive"))
      (node (ref "U1") (pin "40") (pinfunction "PD00_40") (pintype "bidirectional"))
    )
    (net (code "52") (name "Net-(U1-PD01)") (class "Default")
      (node (ref "Q2") (pin "1") (pinfunction "1_1") (pintype "passive"))
      (node (ref "U1") (pin "39") (pinfunction "PD01_39") (pintype "bidirectional"))
    )
    (net (code "53") (name "Net-(U1-SUBG_I0)") (class "Default")
      (node (ref "L4") (pin "2") (pinfunction "2_2") (pintype "passive"))
      (node (ref "U1") (pin "15") (pinfunction "SUBG_I0_15") (pintype "input"))
    )
    (net (code "54") (name "Net-(U1-SUBG_O0)") (class "Default")
      (node (ref "C6") (pin "1") (pinfunction "1_1") (pintype "passive"))
      (node (ref "L5") (pin "2") (pinfunction "2_2") (pintype "passive"))
      (node (ref "U1") (pin "17") (pinfunction "SUBG_O0_17") (pintype "output"))
    )
    (net (code "55") (name "Net-(U5-ILIM)") (class "Default")
      (node (ref "R10") (pin "2") (pinfunction "2_2") (pintype "passive"))
      (node (ref "U5") (pin "12") (pinfunction "ILIM_12") (pintype "bidirectional"))
    )
    (net (code "56") (name "Net-(U5-ISET)") (class "Default")
      (node (ref "R11") (pin "2") (pinfunction "2_2") (pintype "passive"))
      (node (ref "U5") (pin "16") (pinfunction "ISET_16") (pintype "input"))
    )
    (net (code "57") (name "Net-(U5-TMR)") (class "Default")
      (node (ref "R8") (pin "2") (pinfunction "2_2") (pintype "passive"))
      (node (ref "U5") (pin "14") (pinfunction "TMR_14") (pintype "bidirectional"))
    )
    (net (code "58") (name "Net-(U5-TS)") (class "Default")
      (node (ref "R12") (pin "2") (pinfunction "2_2") (pintype "passive"))
      (node (ref "U5") (pin "1") (pinfunction "TS_1") (pintype "input"))
    )
    (net (code "59") (name "Net-(U7-BASE)") (class "Default")
      (node (ref "R9") (pin "2") (pinfunction "2_2") (pintype "passive"))
      (node (ref "U7") (pin "1") (pinfunction "BASE_1") (pintype "input"))
    )
    (net (code "60") (name "Net-(U9A-RSTB)") (class "Default")
      (node (ref "R21") (pin "2") (pinfunction "2_2") (pintype "passive"))
      (node (ref "U9") (pin "9") (pinfunction "RSTB_9") (pintype "passive"))
    )
    (net (code "61") (name "Net-(U9A-VBUS)") (class "Default")
      (node (ref "R18") (pin "2") (pinfunction "2_2") (pintype "passive"))
      (node (ref "R19") (pin "1") (pinfunction "1_1") (pintype "passive"))
      (node (ref "U9") (pin "8") (pinfunction "VBUS_8") (pintype "input"))
    )
    (net (code "62") (name "Net-(U11-BASE)") (class "Default")
      (node (ref "R20") (pin "2") (pinfunction "2_2") (pintype "passive"))
      (node (ref "U11") (pin "1") (pinfunction "BASE_1") (pintype "input"))
    )
    (net (code "63") (name "Net-(U25-FB)") (class "Default")
      (node (ref "R14") (pin "1") (pinfunction "1_1") (pintype "passive"))
      (node (ref "R16") (pin "1") (pinfunction "1_1") (pintype "passive"))
      (node (ref "U25") (pin "9") (pinfunction "FB_9") (pintype "passive"))
    )
    (net (code "64") (name "Net-(U28-I026)") (class "Default")
      (node (ref "R22") (pin "1") (pinfunction "1_1") (pintype "passive"))
      (node (ref "U28") (pin "11") (pinfunction "I026_11") (pintype "bidirectional"))
    )
    (net (code "65") (name "Net-(U28-IO27)") (class "Default")
      (node (ref "R23") (pin "1") (pinfunction "1_1") (pintype "passive"))
      (node (ref "U28") (pin "12") (pinfunction "IO27_12") (pintype "bidirectional"))
    )
    (net (code "66") (name "Net-(X2-ANT)") (class "Default")
      (node (ref "C21") (pin "2") (pinfunction "2_2") (pintype "passive"))
      (node (ref "L4") (pin "1") (pinfunction "1_1") (pintype "passive"))
      (node (ref "X2") (pin "ANTENNA") (pinfunction "ANT_ANTENNA") (pintype "bidirectional"))
    )
    (net (code "67") (name "VBAT") (class "Default")
      (node (ref "E1") (pin "PAD") (pinfunction "P_PAD") (pintype "passive"))
      (node (ref "U5") (pin "2") (pinfunction "BAT_2") (pintype "input"))
    )
    (net (code "68") (name "VDCDC") (class "Default")
      (node (ref "C12") (pin "2") (pinfunction "2_2") (pintype "passive"))
      (node (ref "C13") (pin "2") (pinfunction "2_2") (pintype "passive"))
      (node (ref "C18") (pin "2") (pinfunction "2_2") (pintype "passive"))
      (node (ref "C19") (pin "2") (pinfunction "2_2") (pintype "passive"))
      (node (ref "C22") (pin "2") (pinfunction "2_2") (pintype "passive"))
      (node (ref "C23") (pin "2") (pinfunction "2_2") (pintype "passive"))
      (node (ref "C7") (pin "2") (pinfunction "2_2") (pintype "passive"))
      (node (ref "L2") (pin "2") (pinfunction "2_2") (pintype "passive"))
      (node (ref "U1") (pin "12") (pinfunction "RFVDD_12") (pintype "power_in"))
      (node (ref "U1") (pin "18") (pinfunction "PAVDD_18") (pintype "power_in"))
      (node (ref "U1") (pin "34") (pinfunction "DVDD_34") (pintype "power_in"))
    )
    (net (code "69") (name "VDD") (class "Default")
      (node (ref "C10") (pin "2") (pinfunction "2_2") (pintype "passive"))
      (node (ref "C11") (pin "2") (pinfunction "2_2") (pintype "passive"))
      (node (ref "C15") (pin "2") (pinfunction "2_2") (pintype "passive"))
      (node (ref "C17") (pin "2") (pinfunction "2_2") (pintype "passive"))
      (node (ref "C28") (pin "1") (pinfunction "1_1") (pintype "passive"))
      (node (ref "C32") (pin "1") (pinfunction "1_1") (pintype "passive"))
      (node (ref "C35") (pin "1") (pinfunction "1_1") (pintype "passive"))
      (node (ref "C36") (pin "1") (pinfunction "1_1") (pintype "passive"))
      (node (ref "C37") (pin "1") (pinfunction "1_1") (pintype "passive"))
      (node (ref "C39") (pin "1") (pinfunction "1_1") (pintype "passive"))
      (node (ref "C8") (pin "2") (pinfunction "2_2") (pintype "passive"))
      (node (ref "R13") (pin "2") (pinfunction "2_2") (pintype "passive"))
      (node (ref "R14") (pin "2") (pinfunction "2_2") (pintype "passive"))
      (node (ref "R15") (pin "2") (pinfunction "2_2") (pintype "passive"))
      (node (ref "R17") (pin "2") (pinfunction "2_2") (pintype "passive"))
      (node (ref "R2") (pin "2") (pinfunction "2_2") (pintype "passive"))
      (node (ref "R21") (pin "1") (pinfunction "1_1") (pintype "passive"))
      (node (ref "SV1") (pin "1") (pinfunction "1_1") (pintype "passive"))
      (node (ref "U1") (pin "32") (pinfunction "VREGVDD_32") (pintype "power_in"))
      (node (ref "U1") (pin "35") (pinfunction "AVDD_35") (pintype "power_in"))
      (node (ref "U1") (pin "36") (pinfunction "IOVDD_36") (pintype "power_in"))
      (node (ref "U25") (pin "7") (pinfunction "VOUT_2_7") (pintype "passive"))
      (node (ref "U25") (pin "8") (pinfunction "VOUT_8") (pintype "passive"))
      (node (ref "U28") (pin "2") (pinfunction "3V3_2") (pintype "power_in"))
      (node (ref "U9") (pin "6") (pinfunction "VDD_6") (pintype "power_in"))
      (node (ref "U9") (pin "7") (pinfunction "VREGIN_7") (pintype "power_in"))
      (node (ref "X1") (pin "1") (pinfunction "B_1") (pintype "passive"))
    )
    (net (code "70") (name "VPROC") (class "Default")
      (node (ref "C26") (pin "1") (pinfunction "1_1") (pintype "passive"))
      (node (ref "C27") (pin "1") (pinfunction "1_1") (pintype "passive"))
      (node (ref "C30") (pin "1") (pinfunction "1_1") (pintype "passive"))
      (node (ref "U25") (pin "1") (pinfunction "VIN_2_1") (pintype "passive"))
      (node (ref "U25") (pin "14") (pinfunction "VIN_14") (pintype "passive"))
      (node (ref "U25") (pin "2") (pinfunction "EN_2") (pintype "passive"))
      (node (ref "U5") (pin "10") (pinfunction "OUT_10") (pintype "output"))
      (node (ref "U5") (pin "5") (pinfunction "EN2_5") (pintype "input"))
    )
    (net (code "71") (name "unconnected-(J1-CC1-PadA5)") (class "Default")
      (node (ref "J1") (pin "A5") (pinfunction "CC1_A5") (pintype "bidirectional"))
    )
    (net (code "72") (name "unconnected-(J1-CC2-PadB5)") (class "Default")
      (node (ref "J1") (pin "B5") (pinfunction "CC2_B5") (pintype "bidirectional"))
    )
    (net (code "73") (name "unconnected-(J1-SBU1-PadA8)") (class "Default")
      (node (ref "J1") (pin "A8") (pinfunction "SBU1_A8") (pintype "bidirectional"))
    )
    (net (code "74") (name "unconnected-(J1-SBU2-PadB8)") (class "Default")
      (node (ref "J1") (pin "B8") (pinfunction "SBU2_B8") (pintype "bidirectional"))
    )
    (net (code "75") (name "unconnected-(U1-PA00-Pad21)") (class "Default")
      (node (ref "U1") (pin "21") (pinfunction "PA00_21") (pintype "bidirectional"))
    )
    (net (code "76") (name "unconnected-(U1-PA08-Pad29)") (class "Default")
      (node (ref "U1") (pin "29") (pinfunction "PA08_29") (pintype "bidirectional"))
    )
    (net (code "77") (name "unconnected-(U1-PB00-Pad20)") (class "Default")
      (node (ref "U1") (pin "20") (pinfunction "PB00_20") (pintype "bidirectional"))
    )
    (net (code "78") (name "unconnected-(U1-PB01-Pad19)") (class "Default")
      (node (ref "U1") (pin "19") (pinfunction "PB01_19") (pintype "bidirectional"))
    )
    (net (code "79") (name "unconnected-(U1-PC00-Pad1)") (class "Default")
      (node (ref "U1") (pin "1") (pinfunction "PC00_1") (pintype "bidirectional"))
    )
    (net (code "80") (name "unconnected-(U1-PC01-Pad2)") (class "Default")
      (node (ref "U1") (pin "2") (pinfunction "PC01_2") (pintype "bidirectional"))
    )
    (net (code "81") (name "unconnected-(U1-PD02-Pad38)") (class "Default")
      (node (ref "U1") (pin "38") (pinfunction "PD02_38") (pintype "bidirectional"))
    )
    (net (code "82") (name "unconnected-(U1-PD03-Pad37)") (class "Default")
      (node (ref "U1") (pin "37") (pinfunction "PD03_37") (pintype "bidirectional"))
    )
    (net (code "83") (name "unconnected-(U1-SUBG_I1-Pad14)") (class "Default")
      (node (ref "U1") (pin "14") (pinfunction "SUBG_I1_14") (pintype "input"))
    )
    (net (code "84") (name "unconnected-(U1-SUBG_O1-Pad16)") (class "Default")
      (node (ref "U1") (pin "16") (pinfunction "SUBG_O1_16") (pintype "output"))
    )
    (net (code "85") (name "unconnected-(U9A-CHR0-Pad15)") (class "Default")
      (node (ref "U9") (pin "15") (pinfunction "CHR0_15") (pintype "output"))
    )
    (net (code "86") (name "unconnected-(U9A-CHR1-Pad14)") (class "Default")
      (node (ref "U9") (pin "14") (pinfunction "CHR1_14") (pintype "output"))
    )
    (net (code "87") (name "unconnected-(U9A-CHREN-Pad13)") (class "Default")
      (node (ref "U9") (pin "13") (pinfunction "CHREN_13") (pintype "output"))
    )
    (net (code "88") (name "unconnected-(U9A-CTS-Pad23)") (class "Default")
      (node (ref "U9") (pin "23") (pinfunction "CTS_23") (pintype "input"))
    )
    (net (code "89") (name "unconnected-(U9A-DCD-Pad1)") (class "Default")
      (node (ref "U9") (pin "1") (pinfunction "DCD_1") (pintype "input"))
    )
    (net (code "90") (name "unconnected-(U9A-DSR-Pad27)") (class "Default")
      (node (ref "U9") (pin "27") (pinfunction "DSR_27") (pintype "input"))
    )
    (net (code "91") (name "unconnected-(U9A-GPIO.0{slash}TXT-Pad19)") (class "Default")
      (node (ref "U9") (pin "19") (pinfunction "GPIO.0/TXT_19") (pintype "bidirectional"))
    )
    (net (code "92") (name "unconnected-(U9A-GPIO.1{slash}RXT-Pad18)") (class "Default")
      (node (ref "U9") (pin "18") (pinfunction "GPIO.1/RXT_18") (pintype "bidirectional"))
    )
    (net (code "93") (name "unconnected-(U9A-GPIO.2{slash}RS485-Pad17)") (class "Default")
      (node (ref "U9") (pin "17") (pinfunction "GPIO.2/RS485_17") (pintype "bidirectional"))
    )
    (net (code "94") (name "unconnected-(U9A-GPIO.3{slash}WAKEUP-Pad16)") (class "Default")
      (node (ref "U9") (pin "16") (pinfunction "GPIO.3/WAKEUP_16") (pintype "bidirectional"))
    )
    (net (code "95") (name "unconnected-(U9A-GPIO.4-Pad22)") (class "Default")
      (node (ref "U9") (pin "22") (pinfunction "GPIO.4_22") (pintype "bidirectional"))
    )
    (net (code "96") (name "unconnected-(U9A-GPIO.5-Pad21)") (class "Default")
      (node (ref "U9") (pin "21") (pinfunction "GPIO.5_21") (pintype "bidirectional"))
    )
    (net (code "97") (name "unconnected-(U9A-GPIO.6-Pad20)") (class "Default")
      (node (ref "U9") (pin "20") (pinfunction "GPIO.6_20") (pintype "bidirectional"))
    )
    (net (code "98") (name "unconnected-(U9A-RI{slash}CLK-Pad2)") (class "Default")
      (node (ref "U9") (pin "2") (pinfunction "RI/CLK_2") (pintype "bidirectional"))
    )
    (net (code "99") (name "unconnected-(U9A-SUSPEND-Pad12)") (class "Default")
      (node (ref "U9") (pin "12") (pinfunction "SUSPEND_12") (pintype "output"))
    )
    (net (code "100") (name "unconnected-(U9A-SUSPENDB-Pad11)") (class "Default")
      (node (ref "U9") (pin "11") (pinfunction "SUSPENDB_11") (pintype "output"))
    )
    (net (code "101") (name "unconnected-(U9B-NC-Pad10)") (class "Default")
      (node (ref "U9") (pin "10") (pinfunction "NC_10") (pintype "no_connect"))
    )
    (net (code "102") (name "unconnected-(U12-D1--Pad2)") (class "Default")
      (node (ref "U12") (pin "2") (pinfunction "D1-_2") (pintype "bidirectional"))
    )
    (net (code "103") (name "unconnected-(U12-NC_4-Pad9)") (class "Default")
      (node (ref "U12") (pin "9") (pinfunction "NC_4_9") (pintype "passive"))
    )
    (net (code "104") (name "unconnected-(U25-DNC-Pad5)") (class "Default")
      (node (ref "U25") (pin "5") (pinfunction "DNC_5") (pintype "passive"))
    )
    (net (code "105") (name "unconnected-(U25-DNC_2-Pad4)") (class "Default")
      (node (ref "U25") (pin "4") (pinfunction "DNC_2_4") (pintype "passive"))
    )
    (net (code "106") (name "unconnected-(U25-PGOOD-Pad6)") (class "Default")
      (node (ref "U25") (pin "6") (pinfunction "PGOOD_6") (pintype "passive"))
    )
    (net (code "107") (name "unconnected-(U25-V5V-Pad13)") (class "Default")
      (node (ref "U25") (pin "13") (pinfunction "V5V_13") (pintype "passive"))
    )
    (net (code "108") (name "unconnected-(U28-I034-Pad6)") (class "Default")
      (node (ref "U28") (pin "6") (pinfunction "I034_6") (pintype "input"))
    )
    (net (code "109") (name "unconnected-(U28-I035-Pad7)") (class "Default")
      (node (ref "U28") (pin "7") (pinfunction "I035_7") (pintype "input"))
    )
    (net (code "110") (name "unconnected-(U28-SCL{slash}CLK-Pad20)") (class "Default")
      (node (ref "U28") (pin "20") (pinfunction "SCL/CLK_20") (pintype "bidirectional"))
    )
    (net (code "111") (name "unconnected-(U28-SCS{slash}CMD-Pad19)") (class "Default")
      (node (ref "U28") (pin "19") (pinfunction "SCS/CMD_19") (pintype "bidirectional"))
    )
    (net (code "112") (name "unconnected-(U28-SD1{slash}SD1-Pad22)") (class "Default")
      (node (ref "U28") (pin "22") (pinfunction "SD1/SD1_22") (pintype "bidirectional"))
    )
    (net (code "113") (name "unconnected-(U28-SDO{slash}SD0-Pad21)") (class "Default")
      (node (ref "U28") (pin "21") (pinfunction "SDO/SD0_21") (pintype "bidirectional"))
    )
    (net (code "114") (name "unconnected-(U28-SENSOR_VN-Pad5)") (class "Default")
      (node (ref "U28") (pin "5") (pinfunction "SENSOR_VN_5") (pintype "input"))
    )
    (net (code "115") (name "unconnected-(U28-SENSOR_VP-Pad4)") (class "Default")
      (node (ref "U28") (pin "4") (pinfunction "SENSOR_VP_4") (pintype "input"))
    )
    (net (code "116") (name "unconnected-(U28-SHD{slash}SD2-Pad17)") (class "Default")
      (node (ref "U28") (pin "17") (pinfunction "SHD/SD2_17") (pintype "bidirectional"))
    )
    (net (code "117") (name "unconnected-(U28-SWP{slash}SD3-Pad18)") (class "Default")
      (node (ref "U28") (pin "18") (pinfunction "SWP/SD3_18") (pintype "bidirectional"))
    )
  )
)
